# BaseBoard.net
KiCad netlist of a schematic drawn in Altium Designer
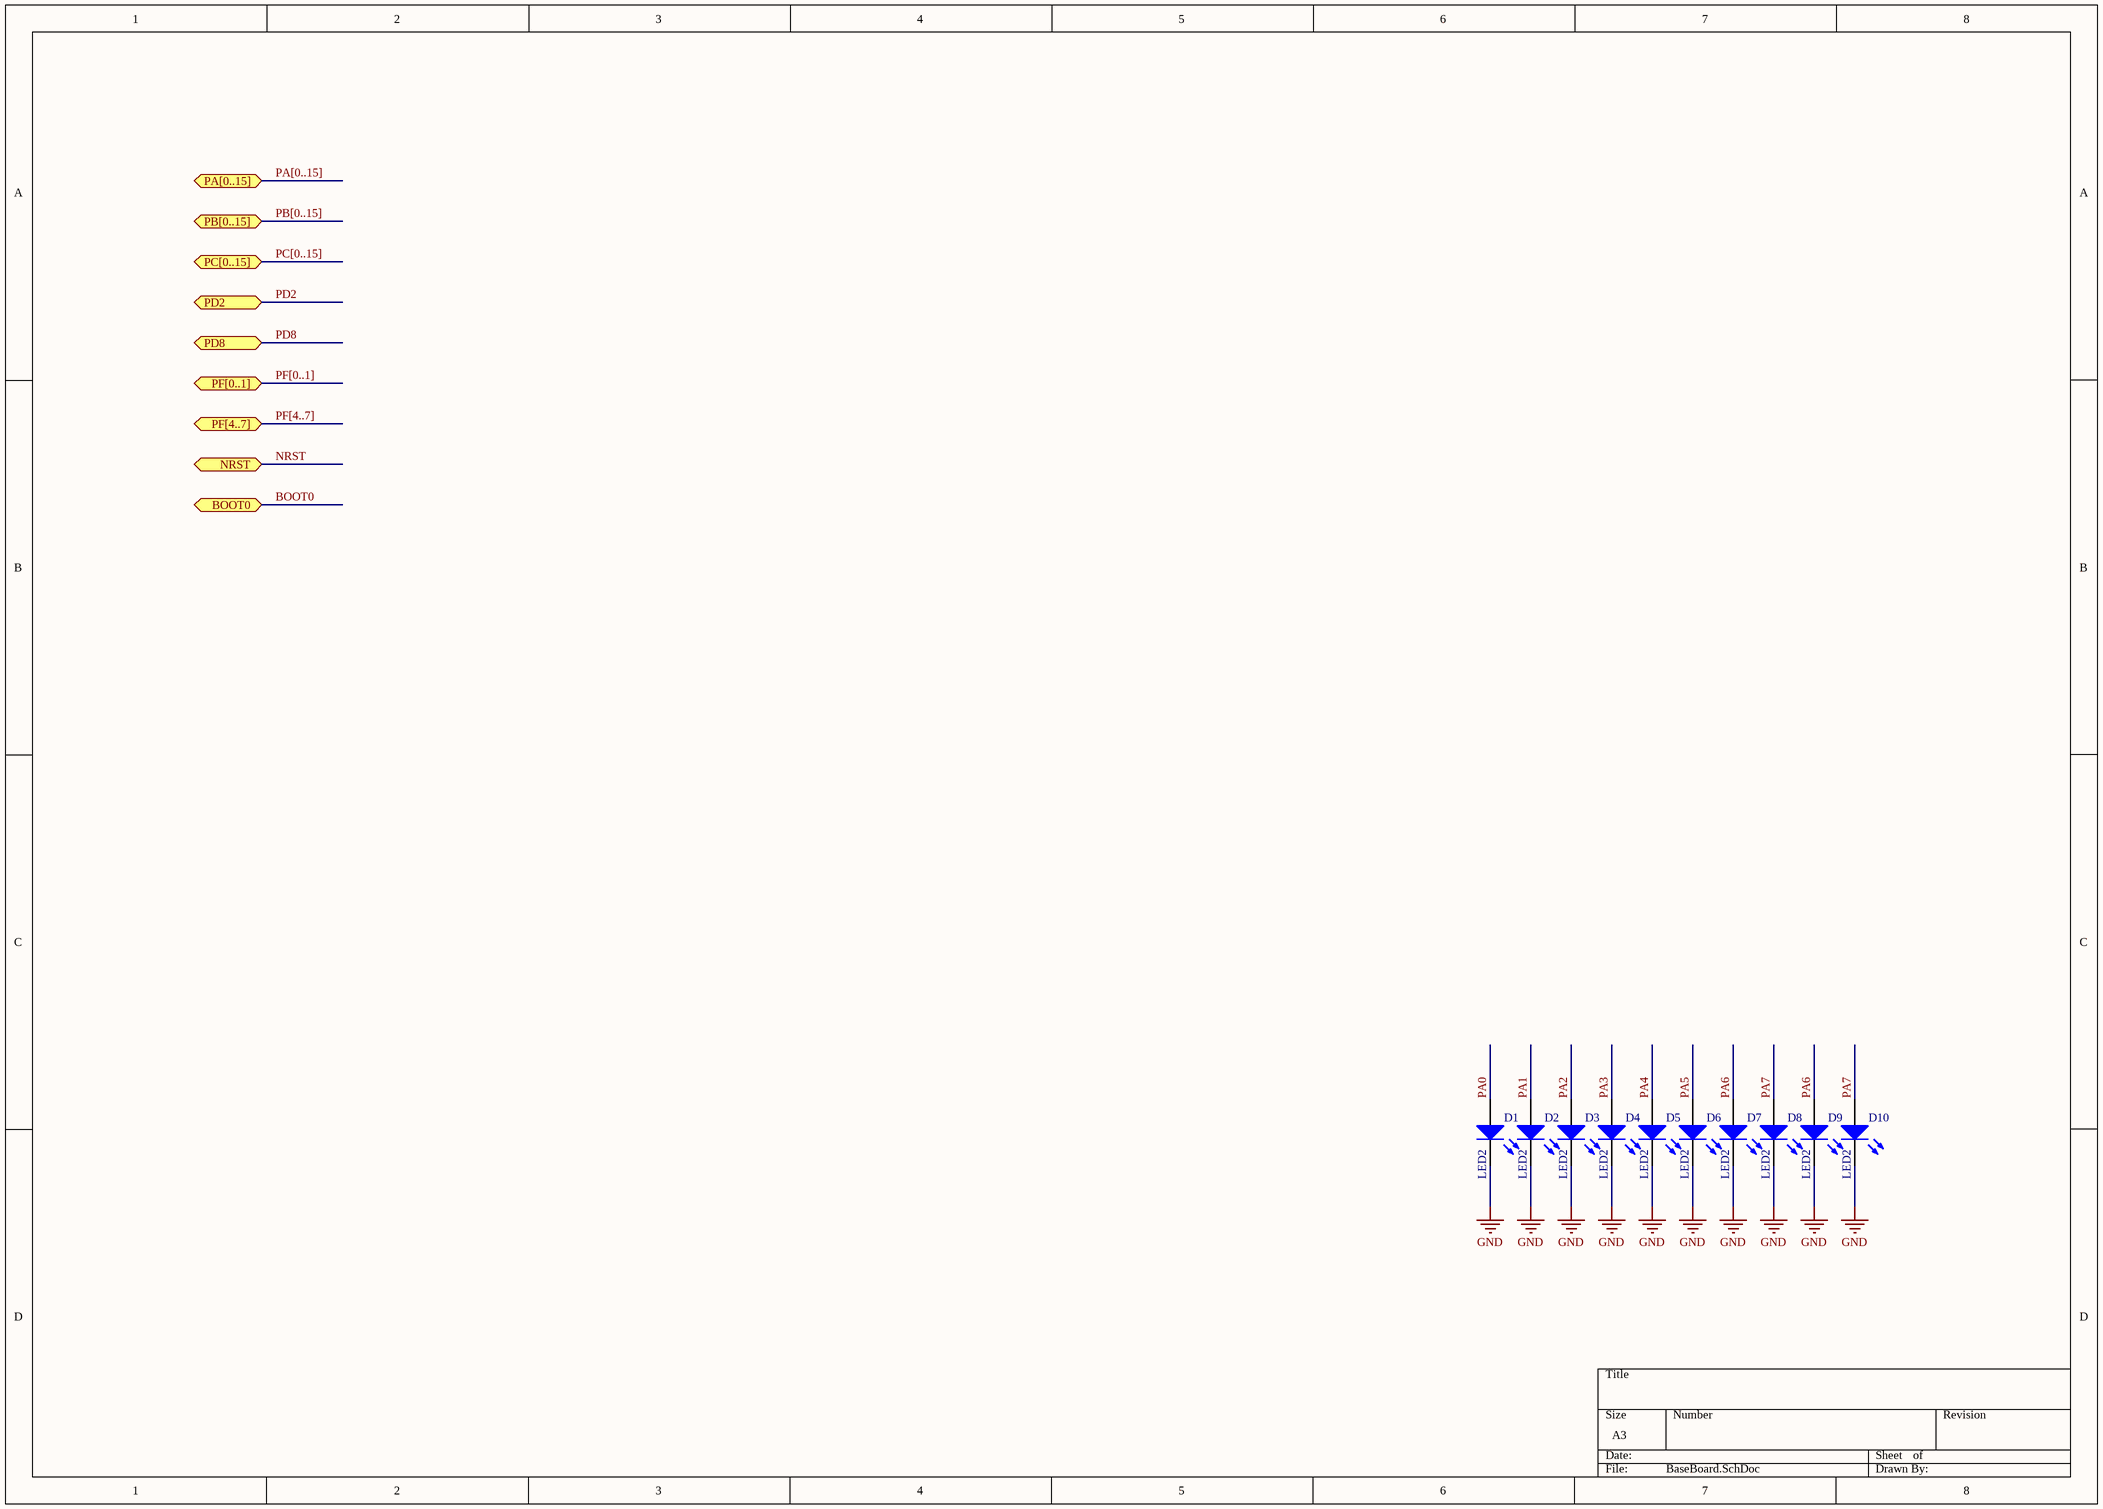
[diagram p0: BaseBoard.SchDoc]

(export (version "E")
  (design (tool "Eeschema 10.0.6"))
  (components
    (comp (ref "D1")
      (value "LED2")
      (footprint "3.2X1.6X1.1")
      (description "Typical RED, GREEN, YELLOW, AMBER GaAs LED")
      (fields (field (name "PUBLISHER") "Altium Limited"))
      (libsource (lib "Miscellaneous Devices") (part "LED2"))
    )
    (comp (ref "D2")
      (value "LED2")
      (footprint "3.2X1.6X1.1")
      (description "Typical RED, GREEN, YELLOW, AMBER GaAs LED")
      (fields (field (name "PUBLISHER") "Altium Limited"))
      (libsource (lib "Miscellaneous Devices") (part "LED2"))
    )
    (comp (ref "D3")
      (value "LED2")
      (footprint "3.2X1.6X1.1")
      (description "Typical RED, GREEN, YELLOW, AMBER GaAs LED")
      (fields (field (name "PUBLISHER") "Altium Limited"))
      (libsource (lib "Miscellaneous Devices") (part "LED2"))
    )
    (comp (ref "D4")
      (value "LED2")
      (footprint "3.2X1.6X1.1")
      (description "Typical RED, GREEN, YELLOW, AMBER GaAs LED")
      (fields (field (name "PUBLISHER") "Altium Limited"))
      (libsource (lib "Miscellaneous Devices") (part "LED2"))
    )
    (comp (ref "D5")
      (value "LED2")
      (footprint "3.2X1.6X1.1")
      (description "Typical RED, GREEN, YELLOW, AMBER GaAs LED")
      (fields (field (name "PUBLISHER") "Altium Limited"))
      (libsource (lib "Miscellaneous Devices") (part "LED2"))
    )
    (comp (ref "D6")
      (value "LED2")
      (footprint "3.2X1.6X1.1")
      (description "Typical RED, GREEN, YELLOW, AMBER GaAs LED")
      (fields (field (name "PUBLISHER") "Altium Limited"))
      (libsource (lib "Miscellaneous Devices") (part "LED2"))
    )
    (comp (ref "D7")
      (value "LED2")
      (footprint "3.2X1.6X1.1")
      (description "Typical RED, GREEN, YELLOW, AMBER GaAs LED")
      (fields (field (name "PUBLISHER") "Altium Limited"))
      (libsource (lib "Miscellaneous Devices") (part "LED2"))
    )
    (comp (ref "D8")
      (value "LED2")
      (footprint "3.2X1.6X1.1")
      (description "Typical RED, GREEN, YELLOW, AMBER GaAs LED")
      (fields (field (name "PUBLISHER") "Altium Limited"))
      (libsource (lib "Miscellaneous Devices") (part "LED2"))
    )
    (comp (ref "D9")
      (value "LED2")
      (footprint "3.2X1.6X1.1")
      (description "Typical RED, GREEN, YELLOW, AMBER GaAs LED")
      (fields (field (name "PUBLISHER") "Altium Limited"))
      (libsource (lib "Miscellaneous Devices") (part "LED2"))
    )
    (comp (ref "D10")
      (value "LED2")
      (footprint "3.2X1.6X1.1")
      (description "Typical RED, GREEN, YELLOW, AMBER GaAs LED")
      (fields (field (name "PUBLISHER") "Altium Limited"))
      (libsource (lib "Miscellaneous Devices") (part "LED2"))
    )
  )
  (nets
    (net (code "49") (name "/PA0") (class "Default")
      (node (ref "D1") (pin "1") (pinfunction "A_1") (pintype "passive"))
    )
    (net (code "50") (name "/PA1") (class "Default")
      (node (ref "D2") (pin "1") (pinfunction "A_1") (pintype "passive"))
    )
    (net (code "51") (name "/PA2") (class "Default")
      (node (ref "D3") (pin "1") (pinfunction "A_1") (pintype "passive"))
    )
    (net (code "52") (name "/PA3") (class "Default")
      (node (ref "D4") (pin "1") (pinfunction "A_1") (pintype "passive"))
    )
    (net (code "53") (name "/PA4") (class "Default")
      (node (ref "D5") (pin "1") (pinfunction "A_1") (pintype "passive"))
    )
    (net (code "54") (name "/PA5") (class "Default")
      (node (ref "D6") (pin "1") (pinfunction "A_1") (pintype "passive"))
    )
    (net (code "55") (name "/PA6") (class "Default")
      (node (ref "D7") (pin "1") (pinfunction "A_1") (pintype "passive"))
      (node (ref "D9") (pin "1") (pinfunction "A_1") (pintype "passive"))
    )
    (net (code "56") (name "/PA7") (class "Default")
      (node (ref "D10") (pin "1") (pinfunction "A_1") (pintype "passive"))
      (node (ref "D8") (pin "1") (pinfunction "A_1") (pintype "passive"))
    )
    (net (code "64") (name "GND") (class "Default")
      (node (ref "D1") (pin "2") (pinfunction "K_2") (pintype "passive"))
      (node (ref "D10") (pin "2") (pinfunction "K_2") (pintype "passive"))
      (node (ref "D2") (pin "2") (pinfunction "K_2") (pintype "passive"))
      (node (ref "D3") (pin "2") (pinfunction "K_2") (pintype "passive"))
      (node (ref "D4") (pin "2") (pinfunction "K_2") (pintype "passive"))
      (node (ref "D5") (pin "2") (pinfunction "K_2") (pintype "passive"))
      (node (ref "D6") (pin "2") (pinfunction "K_2") (pintype "passive"))
      (node (ref "D7") (pin "2") (pinfunction "K_2") (pintype "passive"))
      (node (ref "D8") (pin "2") (pinfunction "K_2") (pintype "passive"))
      (node (ref "D9") (pin "2") (pinfunction "K_2") (pintype "passive"))
    )
  )
)
